# adapter_for_main_board.net
KiCad netlist of a schematic drawn in EAGLE
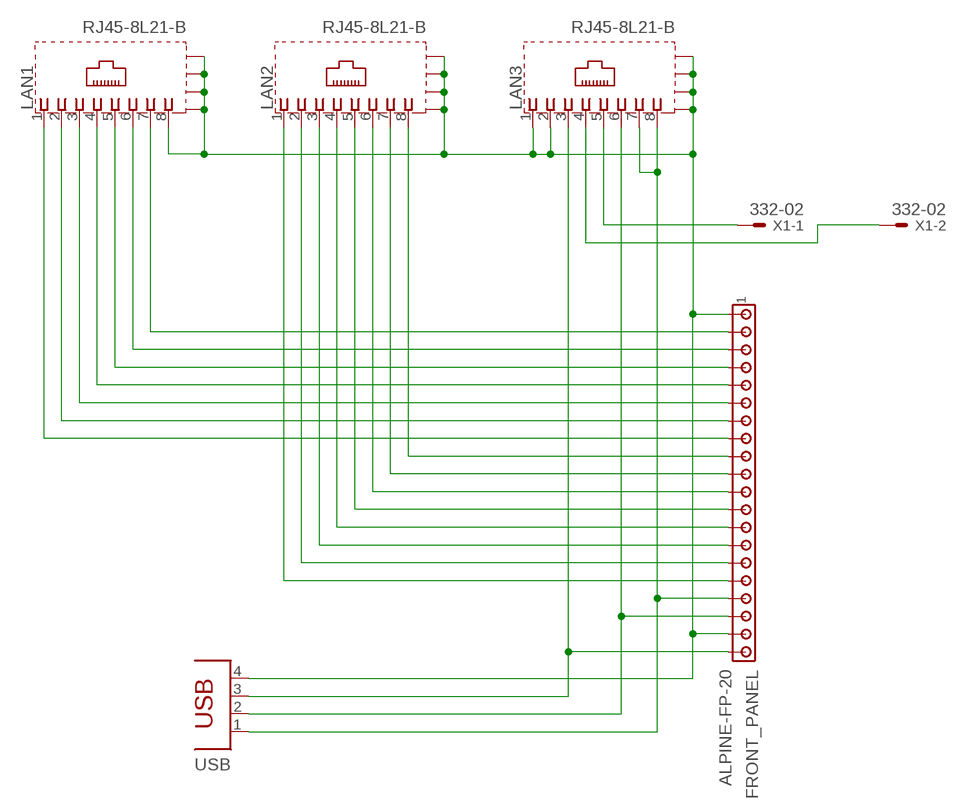
[diagram p0: schematic, sheet 1]

(export (version "E")
  (design (tool "Eeschema 10.0.6"))
  (components
    (comp (ref "FRONT_PANEL")
      (value "ALPINE-FP-20")
      (footprint "eagle-import:ALPINE-FP-20")
      (libsource (lib "eagle-import") (part "ALPINE-FP-20"))
    )
    (comp (ref "LAN1")
      (value "RJ45-8L21-B")
      (footprint "eagle-import:RJ45-SHIELD1")
      (libsource (lib "eagle-import") (part "RJ4521-B-8L"))
    )
    (comp (ref "LAN2")
      (value "RJ45-8L21-B")
      (footprint "eagle-import:RJ45-SHIELD1")
      (libsource (lib "eagle-import") (part "RJ4521-B-8L"))
    )
    (comp (ref "LAN3")
      (value "RJ45-8L21-B")
      (footprint "eagle-import:RJ45-SHIELD1")
      (libsource (lib "eagle-import") (part "RJ4521-B-8L"))
    )
    (comp (ref "USB")
      (value "PN87520")
      (footprint "eagle-import:PN87520")
      (libsource (lib "eagle-import") (part "PN87520"))
    )
    (comp (ref "X1")
      (value "332-02")
      (footprint "eagle-import:332-02")
      (libsource (lib "eagle-import") (part "332-02"))
    )
  )
  (nets
    (net (code "1") (name "Net-(FRONT_PANEL-Pad1)") (class "Default")
      (node (ref "FRONT_PANEL") (pin "1") (pinfunction "1_1") (pintype "passive"))
      (node (ref "FRONT_PANEL") (pin "19") (pinfunction "19_19") (pintype "passive"))
      (node (ref "LAN1") (pin "8") (pinfunction "8_8") (pintype "passive"))
      (node (ref "LAN1") (pin "S1") (pinfunction "S_S1") (pintype "passive"))
      (node (ref "LAN1") (pin "S2") (pinfunction "S_S2") (pintype "passive"))
      (node (ref "LAN1") (pin "S3") (pinfunction "S_S3") (pintype "passive"))
      (node (ref "LAN1") (pin "S4") (pinfunction "S_S4") (pintype "passive"))
      (node (ref "LAN2") (pin "S1") (pinfunction "S_S1") (pintype "passive"))
      (node (ref "LAN2") (pin "S2") (pinfunction "S_S2") (pintype "passive"))
      (node (ref "LAN2") (pin "S3") (pinfunction "S_S3") (pintype "passive"))
      (node (ref "LAN2") (pin "S4") (pinfunction "S_S4") (pintype "passive"))
      (node (ref "LAN3") (pin "1") (pinfunction "1_1") (pintype "passive"))
      (node (ref "LAN3") (pin "2") (pinfunction "2_2") (pintype "passive"))
      (node (ref "LAN3") (pin "S1") (pinfunction "S_S1") (pintype "passive"))
      (node (ref "LAN3") (pin "S2") (pinfunction "S_S2") (pintype "passive"))
      (node (ref "LAN3") (pin "S3") (pinfunction "S_S3") (pintype "passive"))
      (node (ref "LAN3") (pin "S4") (pinfunction "S_S4") (pintype "passive"))
      (node (ref "USB") (pin "4") (pinfunction "4_4") (pintype "passive"))
    )
    (net (code "2") (name "Net-(FRONT_PANEL-Pad2)") (class "Default")
      (node (ref "FRONT_PANEL") (pin "2") (pinfunction "2_2") (pintype "passive"))
      (node (ref "LAN1") (pin "7") (pinfunction "7_7") (pintype "passive"))
    )
    (net (code "3") (name "Net-(FRONT_PANEL-Pad3)") (class "Default")
      (node (ref "FRONT_PANEL") (pin "3") (pinfunction "3_3") (pintype "passive"))
      (node (ref "LAN1") (pin "6") (pinfunction "6_6") (pintype "passive"))
    )
    (net (code "4") (name "Net-(FRONT_PANEL-Pad4)") (class "Default")
      (node (ref "FRONT_PANEL") (pin "4") (pinfunction "4_4") (pintype "passive"))
      (node (ref "LAN1") (pin "5") (pinfunction "5_5") (pintype "passive"))
    )
    (net (code "5") (name "Net-(FRONT_PANEL-Pad5)") (class "Default")
      (node (ref "FRONT_PANEL") (pin "5") (pinfunction "5_5") (pintype "passive"))
      (node (ref "LAN1") (pin "4") (pinfunction "4_4") (pintype "passive"))
    )
    (net (code "6") (name "Net-(FRONT_PANEL-Pad6)") (class "Default")
      (node (ref "FRONT_PANEL") (pin "6") (pinfunction "6_6") (pintype "passive"))
      (node (ref "LAN1") (pin "3") (pinfunction "3_3") (pintype "passive"))
    )
    (net (code "7") (name "Net-(FRONT_PANEL-Pad7)") (class "Default")
      (node (ref "FRONT_PANEL") (pin "7") (pinfunction "7_7") (pintype "passive"))
      (node (ref "LAN1") (pin "2") (pinfunction "2_2") (pintype "passive"))
    )
    (net (code "8") (name "Net-(FRONT_PANEL-Pad8)") (class "Default")
      (node (ref "FRONT_PANEL") (pin "8") (pinfunction "8_8") (pintype "passive"))
      (node (ref "LAN1") (pin "1") (pinfunction "1_1") (pintype "passive"))
    )
    (net (code "9") (name "Net-(FRONT_PANEL-Pad9)") (class "Default")
      (node (ref "FRONT_PANEL") (pin "9") (pinfunction "9_9") (pintype "passive"))
      (node (ref "LAN2") (pin "8") (pinfunction "8_8") (pintype "passive"))
    )
    (net (code "10") (name "Net-(FRONT_PANEL-Pad10)") (class "Default")
      (node (ref "FRONT_PANEL") (pin "10") (pinfunction "10_10") (pintype "passive"))
      (node (ref "LAN2") (pin "7") (pinfunction "7_7") (pintype "passive"))
    )
    (net (code "11") (name "Net-(FRONT_PANEL-Pad11)") (class "Default")
      (node (ref "FRONT_PANEL") (pin "11") (pinfunction "11_11") (pintype "passive"))
      (node (ref "LAN2") (pin "6") (pinfunction "6_6") (pintype "passive"))
    )
    (net (code "12") (name "Net-(FRONT_PANEL-Pad12)") (class "Default")
      (node (ref "FRONT_PANEL") (pin "12") (pinfunction "12_12") (pintype "passive"))
      (node (ref "LAN2") (pin "5") (pinfunction "5_5") (pintype "passive"))
    )
    (net (code "13") (name "Net-(FRONT_PANEL-Pad13)") (class "Default")
      (node (ref "FRONT_PANEL") (pin "13") (pinfunction "13_13") (pintype "passive"))
      (node (ref "LAN2") (pin "4") (pinfunction "4_4") (pintype "passive"))
    )
    (net (code "14") (name "Net-(FRONT_PANEL-Pad14)") (class "Default")
      (node (ref "FRONT_PANEL") (pin "14") (pinfunction "14_14") (pintype "passive"))
      (node (ref "LAN2") (pin "3") (pinfunction "3_3") (pintype "passive"))
    )
    (net (code "15") (name "Net-(FRONT_PANEL-Pad15)") (class "Default")
      (node (ref "FRONT_PANEL") (pin "15") (pinfunction "15_15") (pintype "passive"))
      (node (ref "LAN2") (pin "2") (pinfunction "2_2") (pintype "passive"))
    )
    (net (code "16") (name "Net-(FRONT_PANEL-Pad16)") (class "Default")
      (node (ref "FRONT_PANEL") (pin "16") (pinfunction "16_16") (pintype "passive"))
      (node (ref "LAN2") (pin "1") (pinfunction "1_1") (pintype "passive"))
    )
    (net (code "17") (name "Net-(FRONT_PANEL-Pad17)") (class "Default")
      (node (ref "FRONT_PANEL") (pin "17") (pinfunction "17_17") (pintype "passive"))
      (node (ref "LAN3") (pin "7") (pinfunction "7_7") (pintype "passive"))
      (node (ref "LAN3") (pin "8") (pinfunction "8_8") (pintype "passive"))
      (node (ref "USB") (pin "1") (pinfunction "1_1") (pintype "passive"))
    )
    (net (code "18") (name "Net-(FRONT_PANEL-Pad18)") (class "Default")
      (node (ref "FRONT_PANEL") (pin "18") (pinfunction "18_18") (pintype "passive"))
      (node (ref "LAN3") (pin "6") (pinfunction "6_6") (pintype "passive"))
      (node (ref "USB") (pin "2") (pinfunction "2_2") (pintype "passive"))
    )
    (net (code "19") (name "Net-(FRONT_PANEL-Pad20)") (class "Default")
      (node (ref "FRONT_PANEL") (pin "20") (pinfunction "20_20") (pintype "passive"))
      (node (ref "LAN3") (pin "3") (pinfunction "3_3") (pintype "passive"))
      (node (ref "USB") (pin "3") (pinfunction "3_3") (pintype "passive"))
    )
    (net (code "20") (name "Net-(X1A-S)") (class "Default")
      (node (ref "LAN3") (pin "5") (pinfunction "5_5") (pintype "passive"))
      (node (ref "X1") (pin "1") (pinfunction "S_1") (pintype "passive"))
    )
    (net (code "21") (name "Net-(X1B-S)") (class "Default")
      (node (ref "LAN3") (pin "4") (pinfunction "4_4") (pintype "passive"))
      (node (ref "X1") (pin "2") (pinfunction "S_2") (pintype "passive"))
    )
  )
)
